# ProPrj__20260112_2026-01-12.net
KiCad netlist of a schematic drawn in EasyEDA Pro
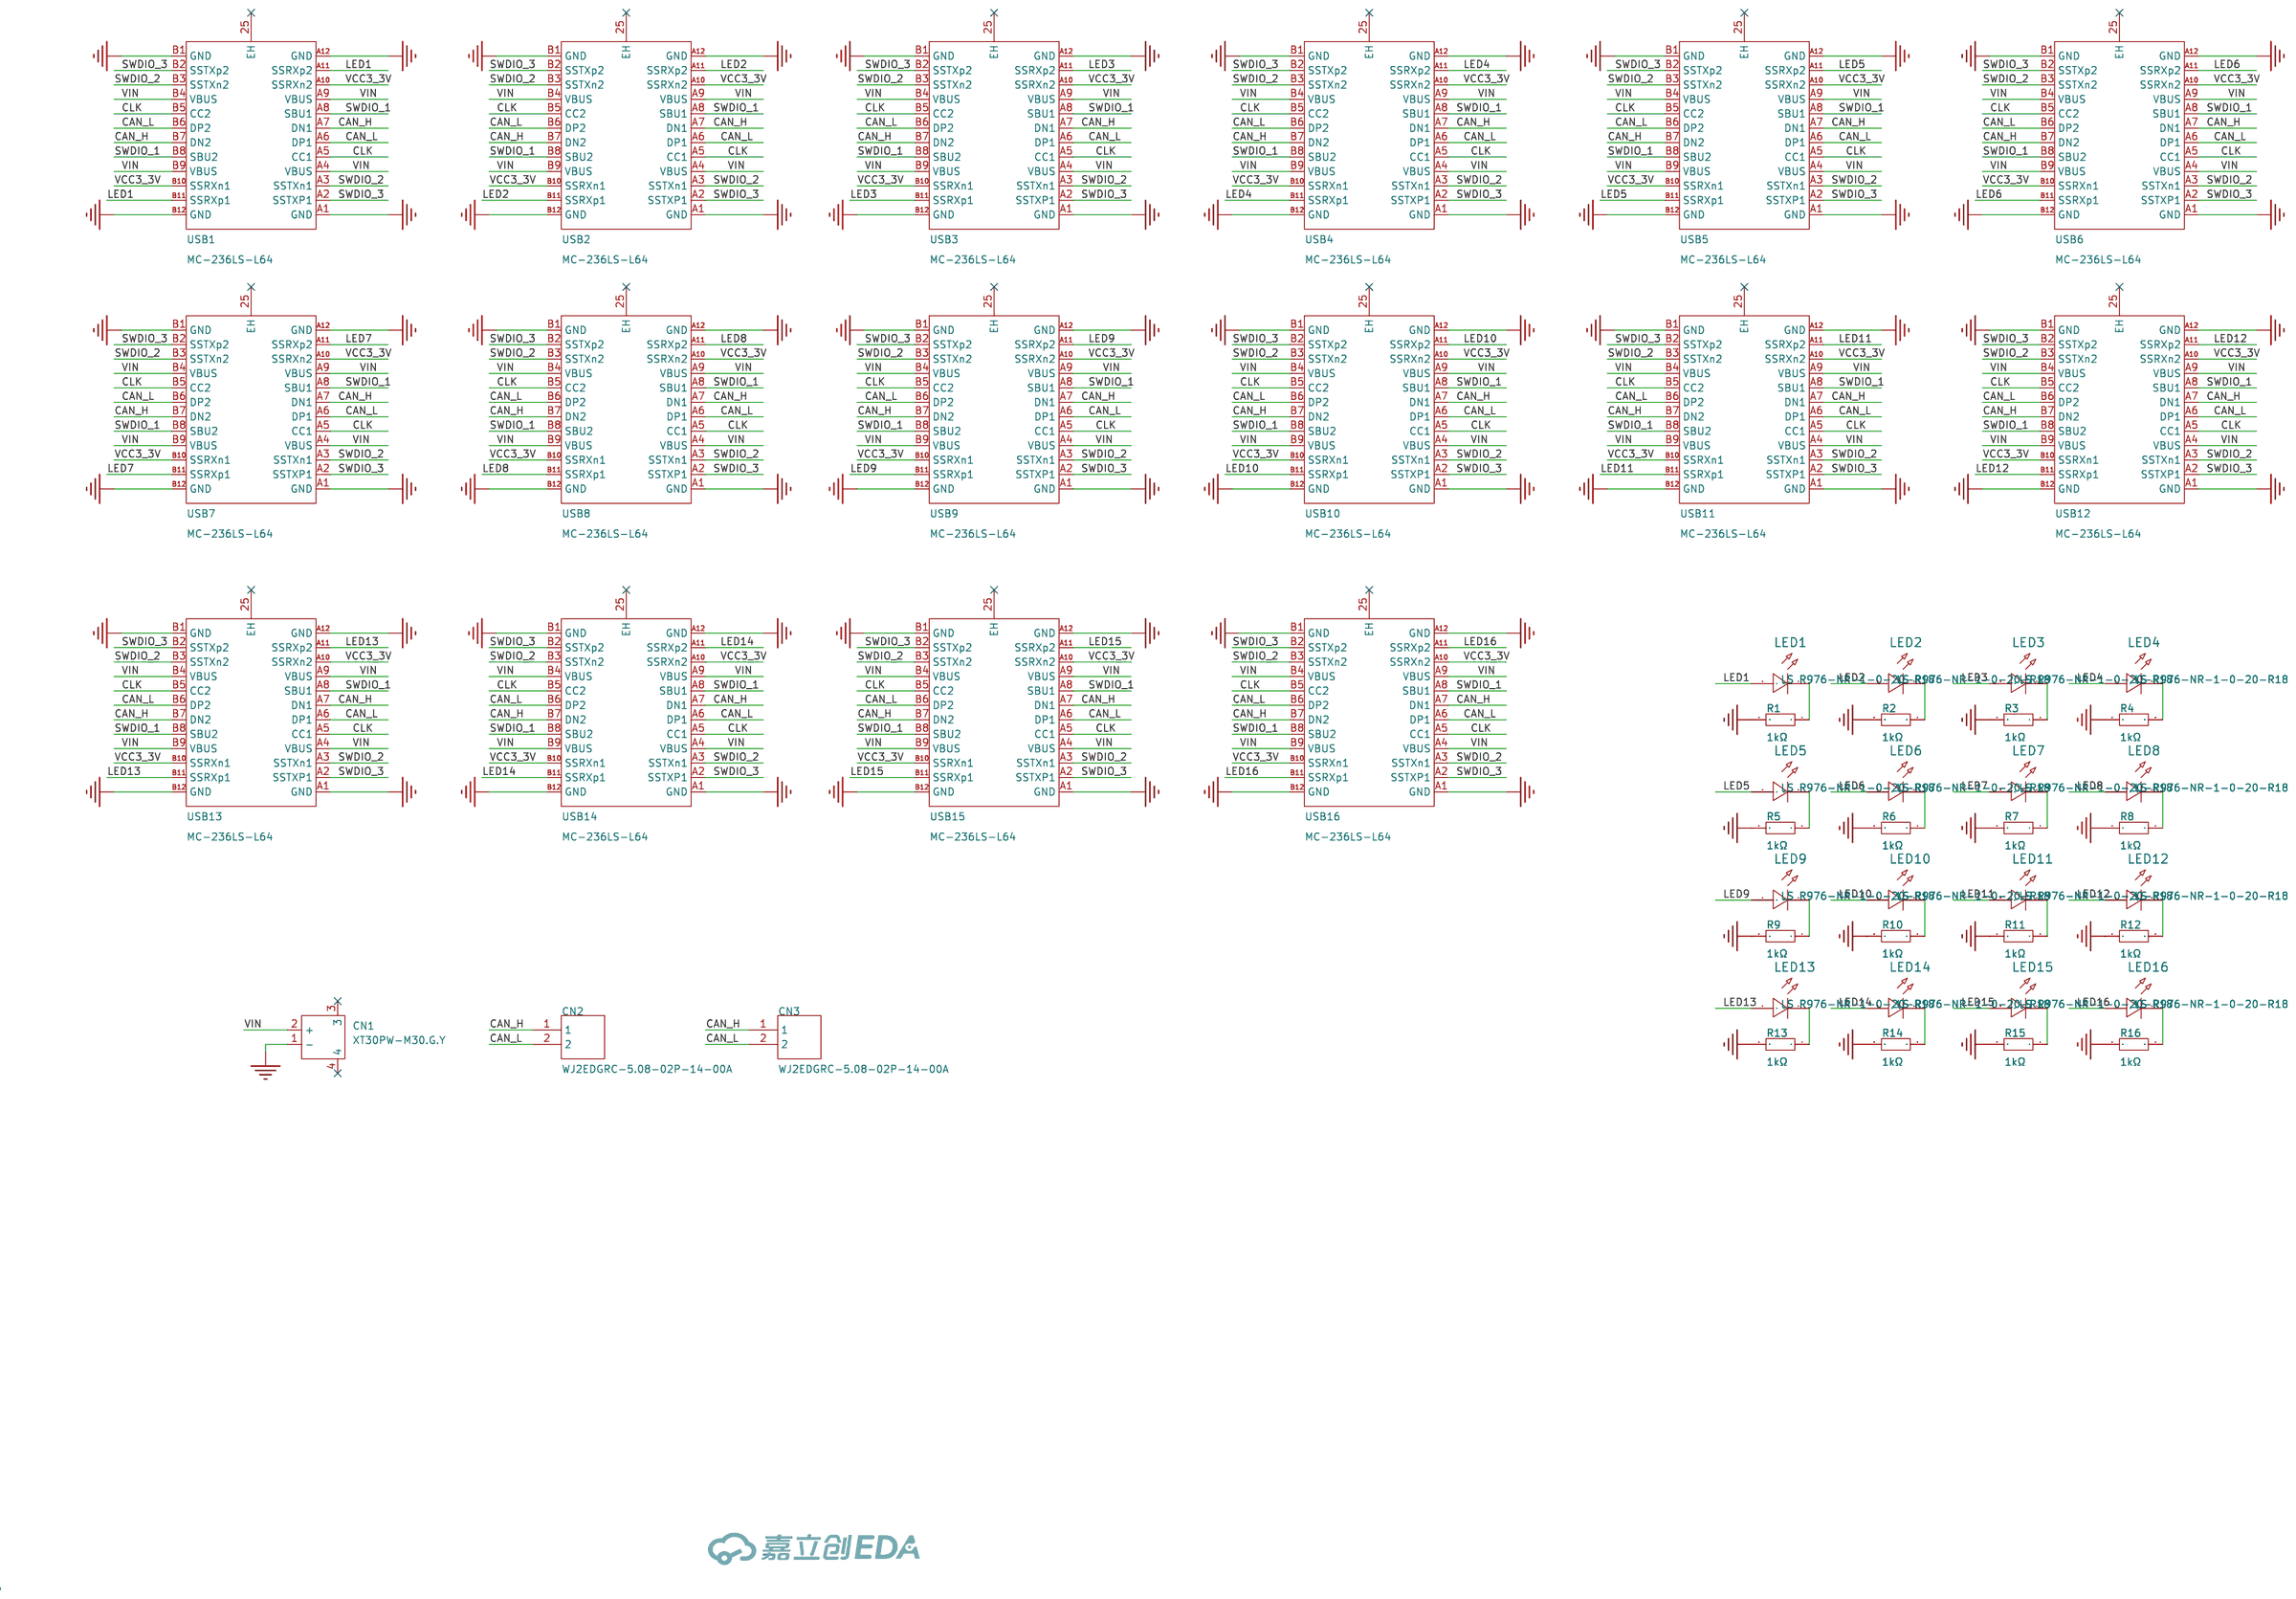
[diagram p0: schematic sheet]

(export (version "E")
  (design (tool "Eeschema 10.0.6"))
  (components
    (comp (ref "CN1")
      (value "XT30PW-M30.G.Y")
      (footprint "easyedapro:CONN-TH_XT30PW-M")
      (description "类别:-;类型1:-;")
      (fields (field (name "Manufacturer") "AMASS(艾迈斯)"))
      (libsource (lib "easyedapro") (part "XT30PW-M"))
    )
    (comp (ref "CN2")
      (value "WJ2EDGRC-5.08-02P-14-00A")
      (footprint "easyedapro:CONN-TH_2P-P5.08_WJ2EDGRC-5.08-2P")
      (fields (field (name "Manufacturer") "KANGNEX(康奈克斯电气)"))
      (libsource (lib "easyedapro") (part "WJ2EDGRC-5.08-2P"))
    )
    (comp (ref "CN3")
      (value "WJ2EDGRC-5.08-02P-14-00A")
      (footprint "easyedapro:CONN-TH_2P-P5.08_WJ2EDGRC-5.08-2P")
      (fields (field (name "Manufacturer") "KANGNEX(康奈克斯电气)"))
      (libsource (lib "easyedapro") (part "WJ2EDGRC-5.08-2P"))
    )
    (comp (ref "LED1")
      (value "LS R976-NR-1-0-20-R18")
      (footprint "easyedapro:LED_0805")
      (fields (field (name "Manufacturer") "OSRAM(欧司朗)"))
      (libsource (lib "easyedapro") (part "LED_R"))
    )
    (comp (ref "LED2")
      (value "LS R976-NR-1-0-20-R18")
      (footprint "easyedapro:LED_0805")
      (fields (field (name "Manufacturer") "OSRAM(欧司朗)"))
      (libsource (lib "easyedapro") (part "LED_R"))
    )
    (comp (ref "LED3")
      (value "LS R976-NR-1-0-20-R18")
      (footprint "easyedapro:LED_0805")
      (fields (field (name "Manufacturer") "OSRAM(欧司朗)"))
      (libsource (lib "easyedapro") (part "LED_R"))
    )
    (comp (ref "LED4")
      (value "LS R976-NR-1-0-20-R18")
      (footprint "easyedapro:LED_0805")
      (fields (field (name "Manufacturer") "OSRAM(欧司朗)"))
      (libsource (lib "easyedapro") (part "LED_R"))
    )
    (comp (ref "LED5")
      (value "LS R976-NR-1-0-20-R18")
      (footprint "easyedapro:LED_0805")
      (fields (field (name "Manufacturer") "OSRAM(欧司朗)"))
      (libsource (lib "easyedapro") (part "LED_R"))
    )
    (comp (ref "LED6")
      (value "LS R976-NR-1-0-20-R18")
      (footprint "easyedapro:LED_0805")
      (fields (field (name "Manufacturer") "OSRAM(欧司朗)"))
      (libsource (lib "easyedapro") (part "LED_R"))
    )
    (comp (ref "LED7")
      (value "LS R976-NR-1-0-20-R18")
      (footprint "easyedapro:LED_0805")
      (fields (field (name "Manufacturer") "OSRAM(欧司朗)"))
      (libsource (lib "easyedapro") (part "LED_R"))
    )
    (comp (ref "LED8")
      (value "LS R976-NR-1-0-20-R18")
      (footprint "easyedapro:LED_0805")
      (fields (field (name "Manufacturer") "OSRAM(欧司朗)"))
      (libsource (lib "easyedapro") (part "LED_R"))
    )
    (comp (ref "LED9")
      (value "LS R976-NR-1-0-20-R18")
      (footprint "easyedapro:LED_0805")
      (fields (field (name "Manufacturer") "OSRAM(欧司朗)"))
      (libsource (lib "easyedapro") (part "LED_R"))
    )
    (comp (ref "LED10")
      (value "LS R976-NR-1-0-20-R18")
      (footprint "easyedapro:LED_0805")
      (fields (field (name "Manufacturer") "OSRAM(欧司朗)"))
      (libsource (lib "easyedapro") (part "LED_R"))
    )
    (comp (ref "LED11")
      (value "LS R976-NR-1-0-20-R18")
      (footprint "easyedapro:LED_0805")
      (fields (field (name "Manufacturer") "OSRAM(欧司朗)"))
      (libsource (lib "easyedapro") (part "LED_R"))
    )
    (comp (ref "LED12")
      (value "LS R976-NR-1-0-20-R18")
      (footprint "easyedapro:LED_0805")
      (fields (field (name "Manufacturer") "OSRAM(欧司朗)"))
      (libsource (lib "easyedapro") (part "LED_R"))
    )
    (comp (ref "LED13")
      (value "LS R976-NR-1-0-20-R18")
      (footprint "easyedapro:LED_0805")
      (fields (field (name "Manufacturer") "OSRAM(欧司朗)"))
      (libsource (lib "easyedapro") (part "LED_R"))
    )
    (comp (ref "LED14")
      (value "LS R976-NR-1-0-20-R18")
      (footprint "easyedapro:LED_0805")
      (fields (field (name "Manufacturer") "OSRAM(欧司朗)"))
      (libsource (lib "easyedapro") (part "LED_R"))
    )
    (comp (ref "LED15")
      (value "LS R976-NR-1-0-20-R18")
      (footprint "easyedapro:LED_0805")
      (fields (field (name "Manufacturer") "OSRAM(欧司朗)"))
      (libsource (lib "easyedapro") (part "LED_R"))
    )
    (comp (ref "LED16")
      (value "LS R976-NR-1-0-20-R18")
      (footprint "easyedapro:LED_0805")
      (fields (field (name "Manufacturer") "OSRAM(欧司朗)"))
      (libsource (lib "easyedapro") (part "LED_R"))
    )
    (comp (ref "R1")
      (value "1kΩ")
      (footprint "easyedapro:R0805")
      (fields
        (field (name "Manufacturer Part") "0805W8F1001T5E")
        (field (name "Manufacturer") "UNI-ROYAL(厚声)")
      )
      (libsource (lib "easyedapro") (part "电阻"))
    )
    (comp (ref "R2")
      (value "1kΩ")
      (footprint "easyedapro:R0805")
      (fields
        (field (name "Manufacturer Part") "0805W8F1001T5E")
        (field (name "Manufacturer") "UNI-ROYAL(厚声)")
      )
      (libsource (lib "easyedapro") (part "电阻"))
    )
    (comp (ref "R3")
      (value "1kΩ")
      (footprint "easyedapro:R0805")
      (fields
        (field (name "Manufacturer Part") "0805W8F1001T5E")
        (field (name "Manufacturer") "UNI-ROYAL(厚声)")
      )
      (libsource (lib "easyedapro") (part "电阻"))
    )
    (comp (ref "R4")
      (value "1kΩ")
      (footprint "easyedapro:R0805")
      (fields
        (field (name "Manufacturer Part") "0805W8F1001T5E")
        (field (name "Manufacturer") "UNI-ROYAL(厚声)")
      )
      (libsource (lib "easyedapro") (part "电阻"))
    )
    (comp (ref "R5")
      (value "1kΩ")
      (footprint "easyedapro:R0805")
      (fields
        (field (name "Manufacturer Part") "0805W8F1001T5E")
        (field (name "Manufacturer") "UNI-ROYAL(厚声)")
      )
      (libsource (lib "easyedapro") (part "电阻"))
    )
    (comp (ref "R6")
      (value "1kΩ")
      (footprint "easyedapro:R0805")
      (fields
        (field (name "Manufacturer Part") "0805W8F1001T5E")
        (field (name "Manufacturer") "UNI-ROYAL(厚声)")
      )
      (libsource (lib "easyedapro") (part "电阻"))
    )
    (comp (ref "R7")
      (value "1kΩ")
      (footprint "easyedapro:R0805")
      (fields
        (field (name "Manufacturer Part") "0805W8F1001T5E")
        (field (name "Manufacturer") "UNI-ROYAL(厚声)")
      )
      (libsource (lib "easyedapro") (part "电阻"))
    )
    (comp (ref "R8")
      (value "1kΩ")
      (footprint "easyedapro:R0805")
      (fields
        (field (name "Manufacturer Part") "0805W8F1001T5E")
        (field (name "Manufacturer") "UNI-ROYAL(厚声)")
      )
      (libsource (lib "easyedapro") (part "电阻"))
    )
    (comp (ref "R9")
      (value "1kΩ")
      (footprint "easyedapro:R0805")
      (fields
        (field (name "Manufacturer Part") "0805W8F1001T5E")
        (field (name "Manufacturer") "UNI-ROYAL(厚声)")
      )
      (libsource (lib "easyedapro") (part "电阻"))
    )
    (comp (ref "R10")
      (value "1kΩ")
      (footprint "easyedapro:R0805")
      (fields
        (field (name "Manufacturer Part") "0805W8F1001T5E")
        (field (name "Manufacturer") "UNI-ROYAL(厚声)")
      )
      (libsource (lib "easyedapro") (part "电阻"))
    )
    (comp (ref "R11")
      (value "1kΩ")
      (footprint "easyedapro:R0805")
      (fields
        (field (name "Manufacturer Part") "0805W8F1001T5E")
        (field (name "Manufacturer") "UNI-ROYAL(厚声)")
      )
      (libsource (lib "easyedapro") (part "电阻"))
    )
    (comp (ref "R12")
      (value "1kΩ")
      (footprint "easyedapro:R0805")
      (fields
        (field (name "Manufacturer Part") "0805W8F1001T5E")
        (field (name "Manufacturer") "UNI-ROYAL(厚声)")
      )
      (libsource (lib "easyedapro") (part "电阻"))
    )
    (comp (ref "R13")
      (value "1kΩ")
      (footprint "easyedapro:R0805")
      (fields
        (field (name "Manufacturer Part") "0805W8F1001T5E")
        (field (name "Manufacturer") "UNI-ROYAL(厚声)")
      )
      (libsource (lib "easyedapro") (part "电阻"))
    )
    (comp (ref "R14")
      (value "1kΩ")
      (footprint "easyedapro:R0805")
      (fields
        (field (name "Manufacturer Part") "0805W8F1001T5E")
        (field (name "Manufacturer") "UNI-ROYAL(厚声)")
      )
      (libsource (lib "easyedapro") (part "电阻"))
    )
    (comp (ref "R15")
      (value "1kΩ")
      (footprint "easyedapro:R0805")
      (fields
        (field (name "Manufacturer Part") "0805W8F1001T5E")
        (field (name "Manufacturer") "UNI-ROYAL(厚声)")
      )
      (libsource (lib "easyedapro") (part "电阻"))
    )
    (comp (ref "R16")
      (value "1kΩ")
      (footprint "easyedapro:R0805")
      (fields
        (field (name "Manufacturer Part") "0805W8F1001T5E")
        (field (name "Manufacturer") "UNI-ROYAL(厚声)")
      )
      (libsource (lib "easyedapro") (part "电阻"))
    )
    (comp (ref "USB1")
      (value "MC-236LS-L64")
      (footprint "easyedapro:TYPE-C-USB-SMD_TYPE-C-31-M-06")
      (description "连接器类型:Type-C;协议标准:USB 3.1;公母:母;安装方式:立贴;触点数量:24P;端口数量:1;额定电流 - 电源:5A;工作温度:-25°C~+85°C;")
      (fields (field (name "Manufacturer") "HANBO(汉博)"))
      (libsource (lib "easyedapro") (part "MC-236LS-L64"))
    )
    (comp (ref "USB2")
      (value "MC-236LS-L64")
      (footprint "easyedapro:TYPE-C-USB-SMD_TYPE-C-31-M-06")
      (description "连接器类型:Type-C;协议标准:USB 3.1;公母:母;安装方式:立贴;触点数量:24P;端口数量:1;额定电流 - 电源:5A;工作温度:-25°C~+85°C;")
      (fields (field (name "Manufacturer") "HANBO(汉博)"))
      (libsource (lib "easyedapro") (part "MC-236LS-L64"))
    )
    (comp (ref "USB3")
      (value "MC-236LS-L64")
      (footprint "easyedapro:TYPE-C-USB-SMD_TYPE-C-31-M-06")
      (description "连接器类型:Type-C;协议标准:USB 3.1;公母:母;安装方式:立贴;触点数量:24P;端口数量:1;额定电流 - 电源:5A;工作温度:-25°C~+85°C;")
      (fields (field (name "Manufacturer") "HANBO(汉博)"))
      (libsource (lib "easyedapro") (part "MC-236LS-L64"))
    )
    (comp (ref "USB4")
      (value "MC-236LS-L64")
      (footprint "easyedapro:TYPE-C-USB-SMD_TYPE-C-31-M-06")
      (description "连接器类型:Type-C;协议标准:USB 3.1;公母:母;安装方式:立贴;触点数量:24P;端口数量:1;额定电流 - 电源:5A;工作温度:-25°C~+85°C;")
      (fields (field (name "Manufacturer") "HANBO(汉博)"))
      (libsource (lib "easyedapro") (part "MC-236LS-L64"))
    )
    (comp (ref "USB5")
      (value "MC-236LS-L64")
      (footprint "easyedapro:TYPE-C-USB-SMD_TYPE-C-31-M-06")
      (description "连接器类型:Type-C;协议标准:USB 3.1;公母:母;安装方式:立贴;触点数量:24P;端口数量:1;额定电流 - 电源:5A;工作温度:-25°C~+85°C;")
      (fields (field (name "Manufacturer") "HANBO(汉博)"))
      (libsource (lib "easyedapro") (part "MC-236LS-L64"))
    )
    (comp (ref "USB6")
      (value "MC-236LS-L64")
      (footprint "easyedapro:TYPE-C-USB-SMD_TYPE-C-31-M-06")
      (description "连接器类型:Type-C;协议标准:USB 3.1;公母:母;安装方式:立贴;触点数量:24P;端口数量:1;额定电流 - 电源:5A;工作温度:-25°C~+85°C;")
      (fields (field (name "Manufacturer") "HANBO(汉博)"))
      (libsource (lib "easyedapro") (part "MC-236LS-L64"))
    )
    (comp (ref "USB7")
      (value "MC-236LS-L64")
      (footprint "easyedapro:TYPE-C-USB-SMD_TYPE-C-31-M-06")
      (description "连接器类型:Type-C;协议标准:USB 3.1;公母:母;安装方式:立贴;触点数量:24P;端口数量:1;额定电流 - 电源:5A;工作温度:-25°C~+85°C;")
      (fields (field (name "Manufacturer") "HANBO(汉博)"))
      (libsource (lib "easyedapro") (part "MC-236LS-L64"))
    )
    (comp (ref "USB8")
      (value "MC-236LS-L64")
      (footprint "easyedapro:TYPE-C-USB-SMD_TYPE-C-31-M-06")
      (description "连接器类型:Type-C;协议标准:USB 3.1;公母:母;安装方式:立贴;触点数量:24P;端口数量:1;额定电流 - 电源:5A;工作温度:-25°C~+85°C;")
      (fields (field (name "Manufacturer") "HANBO(汉博)"))
      (libsource (lib "easyedapro") (part "MC-236LS-L64"))
    )
    (comp (ref "USB9")
      (value "MC-236LS-L64")
      (footprint "easyedapro:TYPE-C-USB-SMD_TYPE-C-31-M-06")
      (description "连接器类型:Type-C;协议标准:USB 3.1;公母:母;安装方式:立贴;触点数量:24P;端口数量:1;额定电流 - 电源:5A;工作温度:-25°C~+85°C;")
      (fields (field (name "Manufacturer") "HANBO(汉博)"))
      (libsource (lib "easyedapro") (part "MC-236LS-L64"))
    )
    (comp (ref "USB10")
      (value "MC-236LS-L64")
      (footprint "easyedapro:TYPE-C-USB-SMD_TYPE-C-31-M-06")
      (description "连接器类型:Type-C;协议标准:USB 3.1;公母:母;安装方式:立贴;触点数量:24P;端口数量:1;额定电流 - 电源:5A;工作温度:-25°C~+85°C;")
      (fields (field (name "Manufacturer") "HANBO(汉博)"))
      (libsource (lib "easyedapro") (part "MC-236LS-L64"))
    )
    (comp (ref "USB11")
      (value "MC-236LS-L64")
      (footprint "easyedapro:TYPE-C-USB-SMD_TYPE-C-31-M-06")
      (description "连接器类型:Type-C;协议标准:USB 3.1;公母:母;安装方式:立贴;触点数量:24P;端口数量:1;额定电流 - 电源:5A;工作温度:-25°C~+85°C;")
      (fields (field (name "Manufacturer") "HANBO(汉博)"))
      (libsource (lib "easyedapro") (part "MC-236LS-L64"))
    )
    (comp (ref "USB12")
      (value "MC-236LS-L64")
      (footprint "easyedapro:TYPE-C-USB-SMD_TYPE-C-31-M-06")
      (description "连接器类型:Type-C;协议标准:USB 3.1;公母:母;安装方式:立贴;触点数量:24P;端口数量:1;额定电流 - 电源:5A;工作温度:-25°C~+85°C;")
      (fields (field (name "Manufacturer") "HANBO(汉博)"))
      (libsource (lib "easyedapro") (part "MC-236LS-L64"))
    )
    (comp (ref "USB13")
      (value "MC-236LS-L64")
      (footprint "easyedapro:TYPE-C-USB-SMD_TYPE-C-31-M-06")
      (description "连接器类型:Type-C;协议标准:USB 3.1;公母:母;安装方式:立贴;触点数量:24P;端口数量:1;额定电流 - 电源:5A;工作温度:-25°C~+85°C;")
      (fields (field (name "Manufacturer") "HANBO(汉博)"))
      (libsource (lib "easyedapro") (part "MC-236LS-L64"))
    )
    (comp (ref "USB14")
      (value "MC-236LS-L64")
      (footprint "easyedapro:TYPE-C-USB-SMD_TYPE-C-31-M-06")
      (description "连接器类型:Type-C;协议标准:USB 3.1;公母:母;安装方式:立贴;触点数量:24P;端口数量:1;额定电流 - 电源:5A;工作温度:-25°C~+85°C;")
      (fields (field (name "Manufacturer") "HANBO(汉博)"))
      (libsource (lib "easyedapro") (part "MC-236LS-L64"))
    )
    (comp (ref "USB15")
      (value "MC-236LS-L64")
      (footprint "easyedapro:TYPE-C-USB-SMD_TYPE-C-31-M-06")
      (description "连接器类型:Type-C;协议标准:USB 3.1;公母:母;安装方式:立贴;触点数量:24P;端口数量:1;额定电流 - 电源:5A;工作温度:-25°C~+85°C;")
      (fields (field (name "Manufacturer") "HANBO(汉博)"))
      (libsource (lib "easyedapro") (part "MC-236LS-L64"))
    )
    (comp (ref "USB16")
      (value "MC-236LS-L64")
      (footprint "easyedapro:TYPE-C-USB-SMD_TYPE-C-31-M-06")
      (description "连接器类型:Type-C;协议标准:USB 3.1;公母:母;安装方式:立贴;触点数量:24P;端口数量:1;额定电流 - 电源:5A;工作温度:-25°C~+85°C;")
      (fields (field (name "Manufacturer") "HANBO(汉博)"))
      (libsource (lib "easyedapro") (part "MC-236LS-L64"))
    )
  )
  (nets
    (net (code "1") (name "/CAN_H") (class "Default")
      (node (ref "CN2") (pin "1") (pinfunction "1_1") (pintype "unspecified"))
      (node (ref "CN3") (pin "1") (pinfunction "1_1") (pintype "unspecified"))
      (node (ref "USB1") (pin "A7") (pinfunction "DN1_A7") (pintype "unspecified"))
      (node (ref "USB1") (pin "B7") (pinfunction "DN2_B7") (pintype "unspecified"))
      (node (ref "USB10") (pin "A7") (pinfunction "DN1_A7") (pintype "unspecified"))
      (node (ref "USB10") (pin "B7") (pinfunction "DN2_B7") (pintype "unspecified"))
      (node (ref "USB11") (pin "A7") (pinfunction "DN1_A7") (pintype "unspecified"))
      (node (ref "USB11") (pin "B7") (pinfunction "DN2_B7") (pintype "unspecified"))
      (node (ref "USB12") (pin "A7") (pinfunction "DN1_A7") (pintype "unspecified"))
      (node (ref "USB12") (pin "B7") (pinfunction "DN2_B7") (pintype "unspecified"))
      (node (ref "USB13") (pin "A7") (pinfunction "DN1_A7") (pintype "unspecified"))
      (node (ref "USB13") (pin "B7") (pinfunction "DN2_B7") (pintype "unspecified"))
      (node (ref "USB14") (pin "A7") (pinfunction "DN1_A7") (pintype "unspecified"))
      (node (ref "USB14") (pin "B7") (pinfunction "DN2_B7") (pintype "unspecified"))
      (node (ref "USB15") (pin "A7") (pinfunction "DN1_A7") (pintype "unspecified"))
      (node (ref "USB15") (pin "B7") (pinfunction "DN2_B7") (pintype "unspecified"))
      (node (ref "USB16") (pin "A7") (pinfunction "DN1_A7") (pintype "unspecified"))
      (node (ref "USB16") (pin "B7") (pinfunction "DN2_B7") (pintype "unspecified"))
      (node (ref "USB2") (pin "A7") (pinfunction "DN1_A7") (pintype "unspecified"))
      (node (ref "USB2") (pin "B7") (pinfunction "DN2_B7") (pintype "unspecified"))
      (node (ref "USB3") (pin "A7") (pinfunction "DN1_A7") (pintype "unspecified"))
      (node (ref "USB3") (pin "B7") (pinfunction "DN2_B7") (pintype "unspecified"))
      (node (ref "USB4") (pin "A7") (pinfunction "DN1_A7") (pintype "unspecified"))
      (node (ref "USB4") (pin "B7") (pinfunction "DN2_B7") (pintype "unspecified"))
      (node (ref "USB5") (pin "A7") (pinfunction "DN1_A7") (pintype "unspecified"))
      (node (ref "USB5") (pin "B7") (pinfunction "DN2_B7") (pintype "unspecified"))
      (node (ref "USB6") (pin "A7") (pinfunction "DN1_A7") (pintype "unspecified"))
      (node (ref "USB6") (pin "B7") (pinfunction "DN2_B7") (pintype "unspecified"))
      (node (ref "USB7") (pin "A7") (pinfunction "DN1_A7") (pintype "unspecified"))
      (node (ref "USB7") (pin "B7") (pinfunction "DN2_B7") (pintype "unspecified"))
      (node (ref "USB8") (pin "A7") (pinfunction "DN1_A7") (pintype "unspecified"))
      (node (ref "USB8") (pin "B7") (pinfunction "DN2_B7") (pintype "unspecified"))
      (node (ref "USB9") (pin "A7") (pinfunction "DN1_A7") (pintype "unspecified"))
      (node (ref "USB9") (pin "B7") (pinfunction "DN2_B7") (pintype "unspecified"))
    )
    (net (code "2") (name "/CAN_L") (class "Default")
      (node (ref "CN2") (pin "2") (pinfunction "2_2") (pintype "unspecified"))
      (node (ref "CN3") (pin "2") (pinfunction "2_2") (pintype "unspecified"))
      (node (ref "USB1") (pin "A6") (pinfunction "DP1_A6") (pintype "unspecified"))
      (node (ref "USB1") (pin "B6") (pinfunction "DP2_B6") (pintype "unspecified"))
      (node (ref "USB10") (pin "A6") (pinfunction "DP1_A6") (pintype "unspecified"))
      (node (ref "USB10") (pin "B6") (pinfunction "DP2_B6") (pintype "unspecified"))
      (node (ref "USB11") (pin "A6") (pinfunction "DP1_A6") (pintype "unspecified"))
      (node (ref "USB11") (pin "B6") (pinfunction "DP2_B6") (pintype "unspecified"))
      (node (ref "USB12") (pin "A6") (pinfunction "DP1_A6") (pintype "unspecified"))
      (node (ref "USB12") (pin "B6") (pinfunction "DP2_B6") (pintype "unspecified"))
      (node (ref "USB13") (pin "A6") (pinfunction "DP1_A6") (pintype "unspecified"))
      (node (ref "USB13") (pin "B6") (pinfunction "DP2_B6") (pintype "unspecified"))
      (node (ref "USB14") (pin "A6") (pinfunction "DP1_A6") (pintype "unspecified"))
      (node (ref "USB14") (pin "B6") (pinfunction "DP2_B6") (pintype "unspecified"))
      (node (ref "USB15") (pin "A6") (pinfunction "DP1_A6") (pintype "unspecified"))
      (node (ref "USB15") (pin "B6") (pinfunction "DP2_B6") (pintype "unspecified"))
      (node (ref "USB16") (pin "A6") (pinfunction "DP1_A6") (pintype "unspecified"))
      (node (ref "USB16") (pin "B6") (pinfunction "DP2_B6") (pintype "unspecified"))
      (node (ref "USB2") (pin "A6") (pinfunction "DP1_A6") (pintype "unspecified"))
      (node (ref "USB2") (pin "B6") (pinfunction "DP2_B6") (pintype "unspecified"))
      (node (ref "USB3") (pin "A6") (pinfunction "DP1_A6") (pintype "unspecified"))
      (node (ref "USB3") (pin "B6") (pinfunction "DP2_B6") (pintype "unspecified"))
      (node (ref "USB4") (pin "A6") (pinfunction "DP1_A6") (pintype "unspecified"))
      (node (ref "USB4") (pin "B6") (pinfunction "DP2_B6") (pintype "unspecified"))
      (node (ref "USB5") (pin "A6") (pinfunction "DP1_A6") (pintype "unspecified"))
      (node (ref "USB5") (pin "B6") (pinfunction "DP2_B6") (pintype "unspecified"))
      (node (ref "USB6") (pin "A6") (pinfunction "DP1_A6") (pintype "unspecified"))
      (node (ref "USB6") (pin "B6") (pinfunction "DP2_B6") (pintype "unspecified"))
      (node (ref "USB7") (pin "A6") (pinfunction "DP1_A6") (pintype "unspecified"))
      (node (ref "USB7") (pin "B6") (pinfunction "DP2_B6") (pintype "unspecified"))
      (node (ref "USB8") (pin "A6") (pinfunction "DP1_A6") (pintype "unspecified"))
      (node (ref "USB8") (pin "B6") (pinfunction "DP2_B6") (pintype "unspecified"))
      (node (ref "USB9") (pin "A6") (pinfunction "DP1_A6") (pintype "unspecified"))
      (node (ref "USB9") (pin "B6") (pinfunction "DP2_B6") (pintype "unspecified"))
    )
    (net (code "3") (name "/CLK") (class "Default")
      (node (ref "USB1") (pin "A5") (pinfunction "CC1_A5") (pintype "unspecified"))
      (node (ref "USB1") (pin "B5") (pinfunction "CC2_B5") (pintype "unspecified"))
      (node (ref "USB10") (pin "A5") (pinfunction "CC1_A5") (pintype "unspecified"))
      (node (ref "USB10") (pin "B5") (pinfunction "CC2_B5") (pintype "unspecified"))
      (node (ref "USB11") (pin "A5") (pinfunction "CC1_A5") (pintype "unspecified"))
      (node (ref "USB11") (pin "B5") (pinfunction "CC2_B5") (pintype "unspecified"))
      (node (ref "USB12") (pin "A5") (pinfunction "CC1_A5") (pintype "unspecified"))
      (node (ref "USB12") (pin "B5") (pinfunction "CC2_B5") (pintype "unspecified"))
      (node (ref "USB13") (pin "A5") (pinfunction "CC1_A5") (pintype "unspecified"))
      (node (ref "USB13") (pin "B5") (pinfunction "CC2_B5") (pintype "unspecified"))
      (node (ref "USB14") (pin "A5") (pinfunction "CC1_A5") (pintype "unspecified"))
      (node (ref "USB14") (pin "B5") (pinfunction "CC2_B5") (pintype "unspecified"))
      (node (ref "USB15") (pin "A5") (pinfunction "CC1_A5") (pintype "unspecified"))
      (node (ref "USB15") (pin "B5") (pinfunction "CC2_B5") (pintype "unspecified"))
      (node (ref "USB16") (pin "A5") (pinfunction "CC1_A5") (pintype "unspecified"))
      (node (ref "USB16") (pin "B5") (pinfunction "CC2_B5") (pintype "unspecified"))
      (node (ref "USB2") (pin "A5") (pinfunction "CC1_A5") (pintype "unspecified"))
      (node (ref "USB2") (pin "B5") (pinfunction "CC2_B5") (pintype "unspecified"))
      (node (ref "USB3") (pin "A5") (pinfunction "CC1_A5") (pintype "unspecified"))
      (node (ref "USB3") (pin "B5") (pinfunction "CC2_B5") (pintype "unspecified"))
      (node (ref "USB4") (pin "A5") (pinfunction "CC1_A5") (pintype "unspecified"))
      (node (ref "USB4") (pin "B5") (pinfunction "CC2_B5") (pintype "unspecified"))
      (node (ref "USB5") (pin "A5") (pinfunction "CC1_A5") (pintype "unspecified"))
      (node (ref "USB5") (pin "B5") (pinfunction "CC2_B5") (pintype "unspecified"))
      (node (ref "USB6") (pin "A5") (pinfunction "CC1_A5") (pintype "unspecified"))
      (node (ref "USB6") (pin "B5") (pinfunction "CC2_B5") (pintype "unspecified"))
      (node (ref "USB7") (pin "A5") (pinfunction "CC1_A5") (pintype "unspecified"))
      (node (ref "USB7") (pin "B5") (pinfunction "CC2_B5") (pintype "unspecified"))
      (node (ref "USB8") (pin "A5") (pinfunction "CC1_A5") (pintype "unspecified"))
      (node (ref "USB8") (pin "B5") (pinfunction "CC2_B5") (pintype "unspecified"))
      (node (ref "USB9") (pin "A5") (pinfunction "CC1_A5") (pintype "unspecified"))
      (node (ref "USB9") (pin "B5") (pinfunction "CC2_B5") (pintype "unspecified"))
    )
    (net (code "4") (name "/LED1") (class "Default")
      (node (ref "LED1") (pin "2") (pinfunction "A_2") (pintype "input"))
      (node (ref "USB1") (pin "A11") (pinfunction "SSRXp2_A11") (pintype "unspecified"))
      (node (ref "USB1") (pin "B11") (pinfunction "SSRXp1_B11") (pintype "unspecified"))
    )
    (net (code "5") (name "/LED2") (class "Default")
      (node (ref "LED2") (pin "2") (pinfunction "A_2") (pintype "input"))
      (node (ref "USB2") (pin "A11") (pinfunction "SSRXp2_A11") (pintype "unspecified"))
      (node (ref "USB2") (pin "B11") (pinfunction "SSRXp1_B11") (pintype "unspecified"))
    )
    (net (code "6") (name "/LED3") (class "Default")
      (node (ref "LED3") (pin "2") (pinfunction "A_2") (pintype "input"))
      (node (ref "USB3") (pin "A11") (pinfunction "SSRXp2_A11") (pintype "unspecified"))
      (node (ref "USB3") (pin "B11") (pinfunction "SSRXp1_B11") (pintype "unspecified"))
    )
    (net (code "7") (name "/LED4") (class "Default")
      (node (ref "LED4") (pin "2") (pinfunction "A_2") (pintype "input"))
      (node (ref "USB4") (pin "A11") (pinfunction "SSRXp2_A11") (pintype "unspecified"))
      (node (ref "USB4") (pin "B11") (pinfunction "SSRXp1_B11") (pintype "unspecified"))
    )
    (net (code "8") (name "/LED5") (class "Default")
      (node (ref "LED5") (pin "2") (pinfunction "A_2") (pintype "input"))
      (node (ref "USB5") (pin "A11") (pinfunction "SSRXp2_A11") (pintype "unspecified"))
      (node (ref "USB5") (pin "B11") (pinfunction "SSRXp1_B11") (pintype "unspecified"))
    )
    (net (code "9") (name "/LED6") (class "Default")
      (node (ref "LED6") (pin "2") (pinfunction "A_2") (pintype "input"))
      (node (ref "USB6") (pin "A11") (pinfunction "SSRXp2_A11") (pintype "unspecified"))
      (node (ref "USB6") (pin "B11") (pinfunction "SSRXp1_B11") (pintype "unspecified"))
    )
    (net (code "10") (name "/LED7") (class "Default")
      (node (ref "LED7") (pin "2") (pinfunction "A_2") (pintype "input"))
      (node (ref "USB7") (pin "A11") (pinfunction "SSRXp2_A11") (pintype "unspecified"))
      (node (ref "USB7") (pin "B11") (pinfunction "SSRXp1_B11") (pintype "unspecified"))
    )
    (net (code "11") (name "/LED8") (class "Default")
      (node (ref "LED8") (pin "2") (pinfunction "A_2") (pintype "input"))
      (node (ref "USB8") (pin "A11") (pinfunction "SSRXp2_A11") (pintype "unspecified"))
      (node (ref "USB8") (pin "B11") (pinfunction "SSRXp1_B11") (pintype "unspecified"))
    )
    (net (code "12") (name "/LED9") (class "Default")
      (node (ref "LED9") (pin "2") (pinfunction "A_2") (pintype "input"))
      (node (ref "USB9") (pin "A11") (pinfunction "SSRXp2_A11") (pintype "unspecified"))
      (node (ref "USB9") (pin "B11") (pinfunction "SSRXp1_B11") (pintype "unspecified"))
    )
    (net (code "13") (name "/LED10") (class "Default")
      (node (ref "LED10") (pin "2") (pinfunction "A_2") (pintype "input"))
      (node (ref "USB10") (pin "A11") (pinfunction "SSRXp2_A11") (pintype "unspecified"))
      (node (ref "USB10") (pin "B11") (pinfunction "SSRXp1_B11") (pintype "unspecified"))
    )
    (net (code "14") (name "/LED11") (class "Default")
      (node (ref "LED11") (pin "2") (pinfunction "A_2") (pintype "input"))
      (node (ref "USB11") (pin "A11") (pinfunction "SSRXp2_A11") (pintype "unspecified"))
      (node (ref "USB11") (pin "B11") (pinfunction "SSRXp1_B11") (pintype "unspecified"))
    )
    (net (code "15") (name "/LED12") (class "Default")
      (node (ref "LED12") (pin "2") (pinfunction "A_2") (pintype "input"))
      (node (ref "USB12") (pin "A11") (pinfunction "SSRXp2_A11") (pintype "unspecified"))
      (node (ref "USB12") (pin "B11") (pinfunction "SSRXp1_B11") (pintype "unspecified"))
    )
    (net (code "16") (name "/LED13") (class "Default")
      (node (ref "LED13") (pin "2") (pinfunction "A_2") (pintype "input"))
      (node (ref "USB13") (pin "A11") (pinfunction "SSRXp2_A11") (pintype "unspecified"))
      (node (ref "USB13") (pin "B11") (pinfunction "SSRXp1_B11") (pintype "unspecified"))
    )
    (net (code "17") (name "/LED14") (class "Default")
      (node (ref "LED14") (pin "2") (pinfunction "A_2") (pintype "input"))
      (node (ref "USB14") (pin "A11") (pinfunction "SSRXp2_A11") (pintype "unspecified"))
      (node (ref "USB14") (pin "B11") (pinfunction "SSRXp1_B11") (pintype "unspecified"))
    )
    (net (code "18") (name "/LED15") (class "Default")
      (node (ref "LED15") (pin "2") (pinfunction "A_2") (pintype "input"))
      (node (ref "USB15") (pin "A11") (pinfunction "SSRXp2_A11") (pintype "unspecified"))
      (node (ref "USB15") (pin "B11") (pinfunction "SSRXp1_B11") (pintype "unspecified"))
    )
    (net (code "19") (name "/LED16") (class "Default")
      (node (ref "LED16") (pin "2") (pinfunction "A_2") (pintype "input"))
      (node (ref "USB16") (pin "A11") (pinfunction "SSRXp2_A11") (pintype "unspecified"))
      (node (ref "USB16") (pin "B11") (pinfunction "SSRXp1_B11") (pintype "unspecified"))
    )
    (net (code "20") (name "/SWDIO_1") (class "Default")
      (node (ref "USB1") (pin "A8") (pinfunction "SBU1_A8") (pintype "unspecified"))
      (node (ref "USB1") (pin "B8") (pinfunction "SBU2_B8") (pintype "unspecified"))
      (node (ref "USB10") (pin "A8") (pinfunction "SBU1_A8") (pintype "unspecified"))
      (node (ref "USB10") (pin "B8") (pinfunction "SBU2_B8") (pintype "unspecified"))
      (node (ref "USB11") (pin "A8") (pinfunction "SBU1_A8") (pintype "unspecified"))
      (node (ref "USB11") (pin "B8") (pinfunction "SBU2_B8") (pintype "unspecified"))
      (node (ref "USB12") (pin "A8") (pinfunction "SBU1_A8") (pintype "unspecified"))
      (node (ref "USB12") (pin "B8") (pinfunction "SBU2_B8") (pintype "unspecified"))
      (node (ref "USB13") (pin "A8") (pinfunction "SBU1_A8") (pintype "unspecified"))
      (node (ref "USB13") (pin "B8") (pinfunction "SBU2_B8") (pintype "unspecified"))
      (node (ref "USB14") (pin "A8") (pinfunction "SBU1_A8") (pintype "unspecified"))
      (node (ref "USB14") (pin "B8") (pinfunction "SBU2_B8") (pintype "unspecified"))
      (node (ref "USB15") (pin "A8") (pinfunction "SBU1_A8") (pintype "unspecified"))
      (node (ref "USB15") (pin "B8") (pinfunction "SBU2_B8") (pintype "unspecified"))
      (node (ref "USB16") (pin "A8") (pinfunction "SBU1_A8") (pintype "unspecified"))
      (node (ref "USB16") (pin "B8") (pinfunction "SBU2_B8") (pintype "unspecified"))
      (node (ref "USB2") (pin "A8") (pinfunction "SBU1_A8") (pintype "unspecified"))
      (node (ref "USB2") (pin "B8") (pinfunction "SBU2_B8") (pintype "unspecified"))
      (node (ref "USB3") (pin "A8") (pinfunction "SBU1_A8") (pintype "unspecified"))
      (node (ref "USB3") (pin "B8") (pinfunction "SBU2_B8") (pintype "unspecified"))
      (node (ref "USB4") (pin "A8") (pinfunction "SBU1_A8") (pintype "unspecified"))
      (node (ref "USB4") (pin "B8") (pinfunction "SBU2_B8") (pintype "unspecified"))
      (node (ref "USB5") (pin "A8") (pinfunction "SBU1_A8") (pintype "unspecified"))
      (node (ref "USB5") (pin "B8") (pinfunction "SBU2_B8") (pintype "unspecified"))
      (node (ref "USB6") (pin "A8") (pinfunction "SBU1_A8") (pintype "unspecified"))
      (node (ref "USB6") (pin "B8") (pinfunction "SBU2_B8") (pintype "unspecified"))
      (node (ref "USB7") (pin "A8") (pinfunction "SBU1_A8") (pintype "unspecified"))
      (node (ref "USB7") (pin "B8") (pinfunction "SBU2_B8") (pintype "unspecified"))
      (node (ref "USB8") (pin "A8") (pinfunction "SBU1_A8") (pintype "unspecified"))
      (node (ref "USB8") (pin "B8") (pinfunction "SBU2_B8") (pintype "unspecified"))
      (node (ref "USB9") (pin "A8") (pinfunction "SBU1_A8") (pintype "unspecified"))
      (node (ref "USB9") (pin "B8") (pinfunction "SBU2_B8") (pintype "unspecified"))
    )
    (net (code "21") (name "/SWDIO_2") (class "Default")
      (node (ref "USB1") (pin "A3") (pinfunction "SSTXn1_A3") (pintype "unspecified"))
      (node (ref "USB1") (pin "B3") (pinfunction "SSTXn2_B3") (pintype "unspecified"))
      (node (ref "USB10") (pin "A3") (pinfunction "SSTXn1_A3") (pintype "unspecified"))
      (node (ref "USB10") (pin "B3") (pinfunction "SSTXn2_B3") (pintype "unspecified"))
      (node (ref "USB11") (pin "A3") (pinfunction "SSTXn1_A3") (pintype "unspecified"))
      (node (ref "USB11") (pin "B3") (pinfunction "SSTXn2_B3") (pintype "unspecified"))
      (node (ref "USB12") (pin "A3") (pinfunction "SSTXn1_A3") (pintype "unspecified"))
      (node (ref "USB12") (pin "B3") (pinfunction "SSTXn2_B3") (pintype "unspecified"))
      (node (ref "USB13") (pin "A3") (pinfunction "SSTXn1_A3") (pintype "unspecified"))
      (node (ref "USB13") (pin "B3") (pinfunction "SSTXn2_B3") (pintype "unspecified"))
      (node (ref "USB14") (pin "A3") (pinfunction "SSTXn1_A3") (pintype "unspecified"))
      (node (ref "USB14") (pin "B3") (pinfunction "SSTXn2_B3") (pintype "unspecified"))
      (node (ref "USB15") (pin "A3") (pinfunction "SSTXn1_A3") (pintype "unspecified"))
      (node (ref "USB15") (pin "B3") (pinfunction "SSTXn2_B3") (pintype "unspecified"))
      (node (ref "USB16") (pin "A3") (pinfunction "SSTXn1_A3") (pintype "unspecified"))
      (node (ref "USB16") (pin "B3") (pinfunction "SSTXn2_B3") (pintype "unspecified"))
      (node (ref "USB2") (pin "A3") (pinfunction "SSTXn1_A3") (pintype "unspecified"))
      (node (ref "USB2") (pin "B3") (pinfunction "SSTXn2_B3") (pintype "unspecified"))
      (node (ref "USB3") (pin "A3") (pinfunction "SSTXn1_A3") (pintype "unspecified"))
      (node (ref "USB3") (pin "B3") (pinfunction "SSTXn2_B3") (pintype "unspecified"))
      (node (ref "USB4") (pin "A3") (pinfunction "SSTXn1_A3") (pintype "unspecified"))
      (node (ref "USB4") (pin "B3") (pinfunction "SSTXn2_B3") (pintype "unspecified"))
      (node (ref "USB5") (pin "A3") (pinfunction "SSTXn1_A3") (pintype "unspecified"))
      (node (ref "USB5") (pin "B3") (pinfunction "SSTXn2_B3") (pintype "unspecified"))
      (node (ref "USB6") (pin "A3") (pinfunction "SSTXn1_A3") (pintype "unspecified"))
      (node (ref "USB6") (pin "B3") (pinfunction "SSTXn2_B3") (pintype "unspecified"))
      (node (ref "USB7") (pin "A3") (pinfunction "SSTXn1_A3") (pintype "unspecified"))
      (node (ref "USB7") (pin "B3") (pinfunction "SSTXn2_B3") (pintype "unspecified"))
      (node (ref "USB8") (pin "A3") (pinfunction "SSTXn1_A3") (pintype "unspecified"))
      (node (ref "USB8") (pin "B3") (pinfunction "SSTXn2_B3") (pintype "unspecified"))
      (node (ref "USB9") (pin "A3") (pinfunction "SSTXn1_A3") (pintype "unspecified"))
      (node (ref "USB9") (pin "B3") (pinfunction "SSTXn2_B3") (pintype "unspecified"))
    )
    (net (code "22") (name "/SWDIO_3") (class "Default")
      (node (ref "USB1") (pin "A2") (pinfunction "SSTXP1_A2") (pintype "unspecified"))
      (node (ref "USB1") (pin "B2") (pinfunction "SSTXp2_B2") (pintype "unspecified"))
      (node (ref "USB10") (pin "A2") (pinfunction "SSTXP1_A2") (pintype "unspecified"))
      (node (ref "USB10") (pin "B2") (pinfunction "SSTXp2_B2") (pintype "unspecified"))
      (node (ref "USB11") (pin "A2") (pinfunction "SSTXP1_A2") (pintype "unspecified"))
      (node (ref "USB11") (pin "B2") (pinfunction "SSTXp2_B2") (pintype "unspecified"))
      (node (ref "USB12") (pin "A2") (pinfunction "SSTXP1_A2") (pintype "unspecified"))
      (node (ref "USB12") (pin "B2") (pinfunction "SSTXp2_B2") (pintype "unspecified"))
      (node (ref "USB13") (pin "A2") (pinfunction "SSTXP1_A2") (pintype "unspecified"))
      (node (ref "USB13") (pin "B2") (pinfunction "SSTXp2_B2") (pintype "unspecified"))
      (node (ref "USB14") (pin "A2") (pinfunction "SSTXP1_A2") (pintype "unspecified"))
      (node (ref "USB14") (pin "B2") (pinfunction "SSTXp2_B2") (pintype "unspecified"))
      (node (ref "USB15") (pin "A2") (pinfunction "SSTXP1_A2") (pintype "unspecified"))
      (node (ref "USB15") (pin "B2") (pinfunction "SSTXp2_B2") (pintype "unspecified"))
      (node (ref "USB16") (pin "A2") (pinfunction "SSTXP1_A2") (pintype "unspecified"))
      (node (ref "USB16") (pin "B2") (pinfunction "SSTXp2_B2") (pintype "unspecified"))
      (node (ref "USB2") (pin "A2") (pinfunction "SSTXP1_A2") (pintype "unspecified"))
      (node (ref "USB2") (pin "B2") (pinfunction "SSTXp2_B2") (pintype "unspecified"))
      (node (ref "USB3") (pin "A2") (pinfunction "SSTXP1_A2") (pintype "unspecified"))
      (node (ref "USB3") (pin "B2") (pinfunction "SSTXp2_B2") (pintype "unspecified"))
      (node (ref "USB4") (pin "A2") (pinfunction "SSTXP1_A2") (pintype "unspecified"))
      (node (ref "USB4") (pin "B2") (pinfunction "SSTXp2_B2") (pintype "unspecified"))
      (node (ref "USB5") (pin "A2") (pinfunction "SSTXP1_A2") (pintype "unspecified"))
      (node (ref "USB5") (pin "B2") (pinfunction "SSTXp2_B2") (pintype "unspecified"))
      (node (ref "USB6") (pin "A2") (pinfunction "SSTXP1_A2") (pintype "unspecified"))
      (node (ref "USB6") (pin "B2") (pinfunction "SSTXp2_B2") (pintype "unspecified"))
      (node (ref "USB7") (pin "A2") (pinfunction "SSTXP1_A2") (pintype "unspecified"))
      (node (ref "USB7") (pin "B2") (pinfunction "SSTXp2_B2") (pintype "unspecified"))
      (node (ref "USB8") (pin "A2") (pinfunction "SSTXP1_A2") (pintype "unspecified"))
      (node (ref "USB8") (pin "B2") (pinfunction "SSTXp2_B2") (pintype "unspecified"))
      (node (ref "USB9") (pin "A2") (pinfunction "SSTXP1_A2") (pintype "unspecified"))
      (node (ref "USB9") (pin "B2") (pinfunction "SSTXp2_B2") (pintype "unspecified"))
    )
    (net (code "23") (name "/VCC3_3V") (class "Default")
      (node (ref "USB1") (pin "A10") (pinfunction "SSRXn2_A10") (pintype "unspecified"))
      (node (ref "USB1") (pin "B10") (pinfunction "SSRXn1_B10") (pintype "unspecified"))
      (node (ref "USB10") (pin "A10") (pinfunction "SSRXn2_A10") (pintype "unspecified"))
      (node (ref "USB10") (pin "B10") (pinfunction "SSRXn1_B10") (pintype "unspecified"))
      (node (ref "USB11") (pin "A10") (pinfunction "SSRXn2_A10") (pintype "unspecified"))
      (node (ref "USB11") (pin "B10") (pinfunction "SSRXn1_B10") (pintype "unspecified"))
      (node (ref "USB12") (pin "A10") (pinfunction "SSRXn2_A10") (pintype "unspecified"))
      (node (ref "USB12") (pin "B10") (pinfunction "SSRXn1_B10") (pintype "unspecified"))
      (node (ref "USB13") (pin "A10") (pinfunction "SSRXn2_A10") (pintype "unspecified"))
      (node (ref "USB13") (pin "B10") (pinfunction "SSRXn1_B10") (pintype "unspecified"))
      (node (ref "USB14") (pin "A10") (pinfunction "SSRXn2_A10") (pintype "unspecified"))
      (node (ref "USB14") (pin "B10") (pinfunction "SSRXn1_B10") (pintype "unspecified"))
      (node (ref "USB15") (pin "A10") (pinfunction "SSRXn2_A10") (pintype "unspecified"))
      (node (ref "USB15") (pin "B10") (pinfunction "SSRXn1_B10") (pintype "unspecified"))
      (node (ref "USB16") (pin "A10") (pinfunction "SSRXn2_A10") (pintype "unspecified"))
      (node (ref "USB16") (pin "B10") (pinfunction "SSRXn1_B10") (pintype "unspecified"))
      (node (ref "USB2") (pin "A10") (pinfunction "SSRXn2_A10") (pintype "unspecified"))
      (node (ref "USB2") (pin "B10") (pinfunction "SSRXn1_B10") (pintype "unspecified"))
      (node (ref "USB3") (pin "A10") (pinfunction "SSRXn2_A10") (pintype "unspecified"))
      (node (ref "USB3") (pin "B10") (pinfunction "SSRXn1_B10") (pintype "unspecified"))
      (node (ref "USB4") (pin "A10") (pinfunction "SSRXn2_A10") (pintype "unspecified"))
      (node (ref "USB4") (pin "B10") (pinfunction "SSRXn1_B10") (pintype "unspecified"))
      (node (ref "USB5") (pin "A10") (pinfunction "SSRXn2_A10") (pintype "unspecified"))
      (node (ref "USB5") (pin "B10") (pinfunction "SSRXn1_B10") (pintype "unspecified"))
      (node (ref "USB6") (pin "A10") (pinfunction "SSRXn2_A10") (pintype "unspecified"))
      (node (ref "USB6") (pin "B10") (pinfunction "SSRXn1_B10") (pintype "unspecified"))
      (node (ref "USB7") (pin "A10") (pinfunction "SSRXn2_A10") (pintype "unspecified"))
      (node (ref "USB7") (pin "B10") (pinfunction "SSRXn1_B10") (pintype "unspecified"))
      (node (ref "USB8") (pin "A10") (pinfunction "SSRXn2_A10") (pintype "unspecified"))
      (node (ref "USB8") (pin "B10") (pinfunction "SSRXn1_B10") (pintype "unspecified"))
      (node (ref "USB9") (pin "A10") (pinfunction "SSRXn2_A10") (pintype "unspecified"))
      (node (ref "USB9") (pin "B10") (pinfunction "SSRXn1_B10") (pintype "unspecified"))
    )
    (net (code "24") (name "/VIN") (class "Default")
      (node (ref "CN1") (pin "2") (pinfunction "+_2") (pintype "unspecified"))
      (node (ref "USB1") (pin "A4") (pinfunction "VBUS_A4") (pintype "unspecified"))
      (node (ref "USB1") (pin "A9") (pinfunction "VBUS_A9") (pintype "unspecified"))
      (node (ref "USB1") (pin "B4") (pinfunction "VBUS_B4") (pintype "unspecified"))
      (node (ref "USB1") (pin "B9") (pinfunction "VBUS_B9") (pintype "unspecified"))
      (node (ref "USB10") (pin "A4") (pinfunction "VBUS_A4") (pintype "unspecified"))
      (node (ref "USB10") (pin "A9") (pinfunction "VBUS_A9") (pintype "unspecified"))
      (node (ref "USB10") (pin "B4") (pinfunction "VBUS_B4") (pintype "unspecified"))
      (node (ref "USB10") (pin "B9") (pinfunction "VBUS_B9") (pintype "unspecified"))
      (node (ref "USB11") (pin "A4") (pinfunction "VBUS_A4") (pintype "unspecified"))
      (node (ref "USB11") (pin "A9") (pinfunction "VBUS_A9") (pintype "unspecified"))
      (node (ref "USB11") (pin "B4") (pinfunction "VBUS_B4") (pintype "unspecified"))
      (node (ref "USB11") (pin "B9") (pinfunction "VBUS_B9") (pintype "unspecified"))
      (node (ref "USB12") (pin "A4") (pinfunction "VBUS_A4") (pintype "unspecified"))
      (node (ref "USB12") (pin "A9") (pinfunction "VBUS_A9") (pintype "unspecified"))
      (node (ref "USB12") (pin "B4") (pinfunction "VBUS_B4") (pintype "unspecified"))
      (node (ref "USB12") (pin "B9") (pinfunction "VBUS_B9") (pintype "unspecified"))
      (node (ref "USB13") (pin "A4") (pinfunction "VBUS_A4") (pintype "unspecified"))
      (node (ref "USB13") (pin "A9") (pinfunction "VBUS_A9") (pintype "unspecified"))
      (node (ref "USB13") (pin "B4") (pinfunction "VBUS_B4") (pintype "unspecified"))
      (node (ref "USB13") (pin "B9") (pinfunction "VBUS_B9") (pintype "unspecified"))
      (node (ref "USB14") (pin "A4") (pinfunction "VBUS_A4") (pintype "unspecified"))
      (node (ref "USB14") (pin "A9") (pinfunction "VBUS_A9") (pintype "unspecified"))
      (node (ref "USB14") (pin "B4") (pinfunction "VBUS_B4") (pintype "unspecified"))
      (node (ref "USB14") (pin "B9") (pinfunction "VBUS_B9") (pintype "unspecified"))
      (node (ref "USB15") (pin "A4") (pinfunction "VBUS_A4") (pintype "unspecified"))
      (node (ref "USB15") (pin "A9") (pinfunction "VBUS_A9") (pintype "unspecified"))
      (node (ref "USB15") (pin "B4") (pinfunction "VBUS_B4") (pintype "unspecified"))
      (node (ref "USB15") (pin "B9") (pinfunction "VBUS_B9") (pintype "unspecified"))
      (node (ref "USB16") (pin "A4") (pinfunction "VBUS_A4") (pintype "unspecified"))
      (node (ref "USB16") (pin "A9") (pinfunction "VBUS_A9") (pintype "unspecified"))
      (node (ref "USB16") (pin "B4") (pinfunction "VBUS_B4") (pintype "unspecified"))
      (node (ref "USB16") (pin "B9") (pinfunction "VBUS_B9") (pintype "unspecified"))
      (node (ref "USB2") (pin "A4") (pinfunction "VBUS_A4") (pintype "unspecified"))
      (node (ref "USB2") (pin "A9") (pinfunction "VBUS_A9") (pintype "unspecified"))
      (node (ref "USB2") (pin "B4") (pinfunction "VBUS_B4") (pintype "unspecified"))
      (node (ref "USB2") (pin "B9") (pinfunction "VBUS_B9") (pintype "unspecified"))
      (node (ref "USB3") (pin "A4") (pinfunction "VBUS_A4") (pintype "unspecified"))
      (node (ref "USB3") (pin "A9") (pinfunction "VBUS_A9") (pintype "unspecified"))
      (node (ref "USB3") (pin "B4") (pinfunction "VBUS_B4") (pintype "unspecified"))
      (node (ref "USB3") (pin "B9") (pinfunction "VBUS_B9") (pintype "unspecified"))
      (node (ref "USB4") (pin "A4") (pinfunction "VBUS_A4") (pintype "unspecified"))
      (node (ref "USB4") (pin "A9") (pinfunction "VBUS_A9") (pintype "unspecified"))
      (node (ref "USB4") (pin "B4") (pinfunction "VBUS_B4") (pintype "unspecified"))
      (node (ref "USB4") (pin "B9") (pinfunction "VBUS_B9") (pintype "unspecified"))
      (node (ref "USB5") (pin "A4") (pinfunction "VBUS_A4") (pintype "unspecified"))
      (node (ref "USB5") (pin "A9") (pinfunction "VBUS_A9") (pintype "unspecified"))
      (node (ref "USB5") (pin "B4") (pinfunction "VBUS_B4") (pintype "unspecified"))
      (node (ref "USB5") (pin "B9") (pinfunction "VBUS_B9") (pintype "unspecified"))
      (node (ref "USB6") (pin "A4") (pinfunction "VBUS_A4") (pintype "unspecified"))
      (node (ref "USB6") (pin "A9") (pinfunction "VBUS_A9") (pintype "unspecified"))
      (node (ref "USB6") (pin "B4") (pinfunction "VBUS_B4") (pintype "unspecified"))
      (node (ref "USB6") (pin "B9") (pinfunction "VBUS_B9") (pintype "unspecified"))
      (node (ref "USB7") (pin "A4") (pinfunction "VBUS_A4") (pintype "unspecified"))
      (node (ref "USB7") (pin "A9") (pinfunction "VBUS_A9") (pintype "unspecified"))
      (node (ref "USB7") (pin "B4") (pinfunction "VBUS_B4") (pintype "unspecified"))
      (node (ref "USB7") (pin "B9") (pinfunction "VBUS_B9") (pintype "unspecified"))
      (node (ref "USB8") (pin "A4") (pinfunction "VBUS_A4") (pintype "unspecified"))
      (node (ref "USB8") (pin "A9") (pinfunction "VBUS_A9") (pintype "unspecified"))
      (node (ref "USB8") (pin "B4") (pinfunction "VBUS_B4") (pintype "unspecified"))
      (node (ref "USB8") (pin "B9") (pinfunction "VBUS_B9") (pintype "unspecified"))
      (node (ref "USB9") (pin "A4") (pinfunction "VBUS_A4") (pintype "unspecified"))
      (node (ref "USB9") (pin "A9") (pinfunction "VBUS_A9") (pintype "unspecified"))
      (node (ref "USB9") (pin "B4") (pinfunction "VBUS_B4") (pintype "unspecified"))
      (node (ref "USB9") (pin "B9") (pinfunction "VBUS_B9") (pintype "unspecified"))
    )
    (net (code "25") (name "GND") (class "Default")
      (node (ref "CN1") (pin "1") (pinfunction "-_1") (pintype "unspecified"))
      (node (ref "R1") (pin "2") (pinfunction "2_2") (pintype "input"))
      (node (ref "R10") (pin "2") (pinfunction "2_2") (pintype "input"))
      (node (ref "R11") (pin "2") (pinfunction "2_2") (pintype "input"))
      (node (ref "R12") (pin "2") (pinfunction "2_2") (pintype "input"))
      (node (ref "R13") (pin "2") (pinfunction "2_2") (pintype "input"))
      (node (ref "R14") (pin "2") (pinfunction "2_2") (pintype "input"))
      (node (ref "R15") (pin "2") (pinfunction "2_2") (pintype "input"))
      (node (ref "R16") (pin "2") (pinfunction "2_2") (pintype "input"))
      (node (ref "R2") (pin "2") (pinfunction "2_2") (pintype "input"))
      (node (ref "R3") (pin "2") (pinfunction "2_2") (pintype "input"))
      (node (ref "R4") (pin "2") (pinfunction "2_2") (pintype "input"))
      (node (ref "R5") (pin "2") (pinfunction "2_2") (pintype "input"))
      (node (ref "R6") (pin "2") (pinfunction "2_2") (pintype "input"))
      (node (ref "R7") (pin "2") (pinfunction "2_2") (pintype "input"))
      (node (ref "R8") (pin "2") (pinfunction "2_2") (pintype "input"))
      (node (ref "R9") (pin "2") (pinfunction "2_2") (pintype "input"))
      (node (ref "USB1") (pin "A1") (pinfunction "GND_A1") (pintype "unspecified"))
      (node (ref "USB1") (pin "A12") (pinfunction "GND_A12") (pintype "unspecified"))
      (node (ref "USB1") (pin "B1") (pinfunction "GND_B1") (pintype "unspecified"))
      (node (ref "USB1") (pin "B12") (pinfunction "GND_B12") (pintype "unspecified"))
      (node (ref "USB10") (pin "A1") (pinfunction "GND_A1") (pintype "unspecified"))
      (node (ref "USB10") (pin "A12") (pinfunction "GND_A12") (pintype "unspecified"))
      (node (ref "USB10") (pin "B1") (pinfunction "GND_B1") (pintype "unspecified"))
      (node (ref "USB10") (pin "B12") (pinfunction "GND_B12") (pintype "unspecified"))
      (node (ref "USB11") (pin "A1") (pinfunction "GND_A1") (pintype "unspecified"))
      (node (ref "USB11") (pin "A12") (pinfunction "GND_A12") (pintype "unspecified"))
      (node (ref "USB11") (pin "B1") (pinfunction "GND_B1") (pintype "unspecified"))
      (node (ref "USB11") (pin "B12") (pinfunction "GND_B12") (pintype "unspecified"))
      (node (ref "USB12") (pin "A1") (pinfunction "GND_A1") (pintype "unspecified"))
      (node (ref "USB12") (pin "A12") (pinfunction "GND_A12") (pintype "unspecified"))
      (node (ref "USB12") (pin "B1") (pinfunction "GND_B1") (pintype "unspecified"))
      (node (ref "USB12") (pin "B12") (pinfunction "GND_B12") (pintype "unspecified"))
      (node (ref "USB13") (pin "A1") (pinfunction "GND_A1") (pintype "unspecified"))
      (node (ref "USB13") (pin "A12") (pinfunction "GND_A12") (pintype "unspecified"))
      (node (ref "USB13") (pin "B1") (pinfunction "GND_B1") (pintype "unspecified"))
      (node (ref "USB13") (pin "B12") (pinfunction "GND_B12") (pintype "unspecified"))
      (node (ref "USB14") (pin "A1") (pinfunction "GND_A1") (pintype "unspecified"))
      (node (ref "USB14") (pin "A12") (pinfunction "GND_A12") (pintype "unspecified"))
      (node (ref "USB14") (pin "B1") (pinfunction "GND_B1") (pintype "unspecified"))
      (node (ref "USB14") (pin "B12") (pinfunction "GND_B12") (pintype "unspecified"))
      (node (ref "USB15") (pin "A1") (pinfunction "GND_A1") (pintype "unspecified"))
      (node (ref "USB15") (pin "A12") (pinfunction "GND_A12") (pintype "unspecified"))
      (node (ref "USB15") (pin "B1") (pinfunction "GND_B1") (pintype "unspecified"))
      (node (ref "USB15") (pin "B12") (pinfunction "GND_B12") (pintype "unspecified"))
      (node (ref "USB16") (pin "A1") (pinfunction "GND_A1") (pintype "unspecified"))
      (node (ref "USB16") (pin "A12") (pinfunction "GND_A12") (pintype "unspecified"))
      (node (ref "USB16") (pin "B1") (pinfunction "GND_B1") (pintype "unspecified"))
      (node (ref "USB16") (pin "B12") (pinfunction "GND_B12") (pintype "unspecified"))
      (node (ref "USB2") (pin "A1") (pinfunction "GND_A1") (pintype "unspecified"))
      (node (ref "USB2") (pin "A12") (pinfunction "GND_A12") (pintype "unspecified"))
      (node (ref "USB2") (pin "B1") (pinfunction "GND_B1") (pintype "unspecified"))
      (node (ref "USB2") (pin "B12") (pinfunction "GND_B12") (pintype "unspecified"))
      (node (ref "USB3") (pin "A1") (pinfunction "GND_A1") (pintype "unspecified"))
      (node (ref "USB3") (pin "A12") (pinfunction "GND_A12") (pintype "unspecified"))
      (node (ref "USB3") (pin "B1") (pinfunction "GND_B1") (pintype "unspecified"))
      (node (ref "USB3") (pin "B12") (pinfunction "GND_B12") (pintype "unspecified"))
      (node (ref "USB4") (pin "A1") (pinfunction "GND_A1") (pintype "unspecified"))
      (node (ref "USB4") (pin "A12") (pinfunction "GND_A12") (pintype "unspecified"))
      (node (ref "USB4") (pin "B1") (pinfunction "GND_B1") (pintype "unspecified"))
      (node (ref "USB4") (pin "B12") (pinfunction "GND_B12") (pintype "unspecified"))
      (node (ref "USB5") (pin "A1") (pinfunction "GND_A1") (pintype "unspecified"))
      (node (ref "USB5") (pin "A12") (pinfunction "GND_A12") (pintype "unspecified"))
      (node (ref "USB5") (pin "B1") (pinfunction "GND_B1") (pintype "unspecified"))
      (node (ref "USB5") (pin "B12") (pinfunction "GND_B12") (pintype "unspecified"))
      (node (ref "USB6") (pin "A1") (pinfunction "GND_A1") (pintype "unspecified"))
      (node (ref "USB6") (pin "A12") (pinfunction "GND_A12") (pintype "unspecified"))
      (node (ref "USB6") (pin "B1") (pinfunction "GND_B1") (pintype "unspecified"))
      (node (ref "USB6") (pin "B12") (pinfunction "GND_B12") (pintype "unspecified"))
      (node (ref "USB7") (pin "A1") (pinfunction "GND_A1") (pintype "unspecified"))
      (node (ref "USB7") (pin "A12") (pinfunction "GND_A12") (pintype "unspecified"))
      (node (ref "USB7") (pin "B1") (pinfunction "GND_B1") (pintype "unspecified"))
      (node (ref "USB7") (pin "B12") (pinfunction "GND_B12") (pintype "unspecified"))
      (node (ref "USB8") (pin "A1") (pinfunction "GND_A1") (pintype "unspecified"))
      (node (ref "USB8") (pin "A12") (pinfunction "GND_A12") (pintype "unspecified"))
      (node (ref "USB8") (pin "B1") (pinfunction "GND_B1") (pintype "unspecified"))
      (node (ref "USB8") (pin "B12") (pinfunction "GND_B12") (pintype "unspecified"))
      (node (ref "USB9") (pin "A1") (pinfunction "GND_A1") (pintype "unspecified"))
      (node (ref "USB9") (pin "A12") (pinfunction "GND_A12") (pintype "unspecified"))
      (node (ref "USB9") (pin "B1") (pinfunction "GND_B1") (pintype "unspecified"))
      (node (ref "USB9") (pin "B12") (pinfunction "GND_B12") (pintype "unspecified"))
    )
    (net (code "26") (name "Net-(LED1-C)") (class "Default")
      (node (ref "LED1") (pin "1") (pinfunction "C_1") (pintype "input"))
      (node (ref "R1") (pin "1") (pinfunction "1_1") (pintype "input"))
    )
    (net (code "27") (name "Net-(LED2-C)") (class "Default")
      (node (ref "LED2") (pin "1") (pinfunction "C_1") (pintype "input"))
      (node (ref "R2") (pin "1") (pinfunction "1_1") (pintype "input"))
    )
    (net (code "28") (name "Net-(LED3-C)") (class "Default")
      (node (ref "LED3") (pin "1") (pinfunction "C_1") (pintype "input"))
      (node (ref "R3") (pin "1") (pinfunction "1_1") (pintype "input"))
    )
    (net (code "29") (name "Net-(LED4-C)") (class "Default")
      (node (ref "LED4") (pin "1") (pinfunction "C_1") (pintype "input"))
      (node (ref "R4") (pin "1") (pinfunction "1_1") (pintype "input"))
    )
    (net (code "30") (name "Net-(LED5-C)") (class "Default")
      (node (ref "LED5") (pin "1") (pinfunction "C_1") (pintype "input"))
      (node (ref "R5") (pin "1") (pinfunction "1_1") (pintype "input"))
    )
    (net (code "31") (name "Net-(LED6-C)") (class "Default")
      (node (ref "LED6") (pin "1") (pinfunction "C_1") (pintype "input"))
      (node (ref "R6") (pin "1") (pinfunction "1_1") (pintype "input"))
    )
    (net (code "32") (name "Net-(LED7-C)") (class "Default")
      (node (ref "LED7") (pin "1") (pinfunction "C_1") (pintype "input"))
      (node (ref "R7") (pin "1") (pinfunction "1_1") (pintype "input"))
    )
    (net (code "33") (name "Net-(LED8-C)") (class "Default")
      (node (ref "LED8") (pin "1") (pinfunction "C_1") (pintype "input"))
      (node (ref "R8") (pin "1") (pinfunction "1_1") (pintype "input"))
    )
    (net (code "34") (name "Net-(LED9-C)") (class "Default")
      (node (ref "LED9") (pin "1") (pinfunction "C_1") (pintype "input"))
      (node (ref "R9") (pin "1") (pinfunction "1_1") (pintype "input"))
    )
    (net (code "35") (name "Net-(LED10-C)") (class "Default")
      (node (ref "LED10") (pin "1") (pinfunction "C_1") (pintype "input"))
      (node (ref "R10") (pin "1") (pinfunction "1_1") (pintype "input"))
    )
    (net (code "36") (name "Net-(LED11-C)") (class "Default")
      (node (ref "LED11") (pin "1") (pinfunction "C_1") (pintype "input"))
      (node (ref "R11") (pin "1") (pinfunction "1_1") (pintype "input"))
    )
    (net (code "37") (name "Net-(LED12-C)") (class "Default")
      (node (ref "LED12") (pin "1") (pinfunction "C_1") (pintype "input"))
      (node (ref "R12") (pin "1") (pinfunction "1_1") (pintype "input"))
    )
    (net (code "38") (name "Net-(LED13-C)") (class "Default")
      (node (ref "LED13") (pin "1") (pinfunction "C_1") (pintype "input"))
      (node (ref "R13") (pin "1") (pinfunction "1_1") (pintype "input"))
    )
    (net (code "39") (name "Net-(LED14-C)") (class "Default")
      (node (ref "LED14") (pin "1") (pinfunction "C_1") (pintype "input"))
      (node (ref "R14") (pin "1") (pinfunction "1_1") (pintype "input"))
    )
    (net (code "40") (name "Net-(LED15-C)") (class "Default")
      (node (ref "LED15") (pin "1") (pinfunction "C_1") (pintype "input"))
      (node (ref "R15") (pin "1") (pinfunction "1_1") (pintype "input"))
    )
    (net (code "41") (name "Net-(LED16-C)") (class "Default")
      (node (ref "LED16") (pin "1") (pinfunction "C_1") (pintype "input"))
      (node (ref "R16") (pin "1") (pinfunction "1_1") (pintype "input"))
    )
    (net (code "42") (name "unconnected-(CN1-Pad3)") (class "Default")
      (node (ref "CN1") (pin "3") (pinfunction "3_3") (pintype "unspecified+no_connect"))
    )
    (net (code "43") (name "unconnected-(CN1-Pad4)") (class "Default")
      (node (ref "CN1") (pin "4") (pinfunction "4_4") (pintype "unspecified+no_connect"))
    )
    (net (code "44") (name "unconnected-(USB1-EH-Pad25)") (class "Default")
      (node (ref "USB1") (pin "25") (pinfunction "EH_25") (pintype "unspecified+no_connect"))
    )
    (net (code "45") (name "unconnected-(USB2-EH-Pad25)") (class "Default")
      (node (ref "USB2") (pin "25") (pinfunction "EH_25") (pintype "unspecified+no_connect"))
    )
    (net (code "46") (name "unconnected-(USB3-EH-Pad25)") (class "Default")
      (node (ref "USB3") (pin "25") (pinfunction "EH_25") (pintype "unspecified+no_connect"))
    )
    (net (code "47") (name "unconnected-(USB4-EH-Pad25)") (class "Default")
      (node (ref "USB4") (pin "25") (pinfunction "EH_25") (pintype "unspecified+no_connect"))
    )
    (net (code "48") (name "unconnected-(USB5-EH-Pad25)") (class "Default")
      (node (ref "USB5") (pin "25") (pinfunction "EH_25") (pintype "unspecified+no_connect"))
    )
    (net (code "49") (name "unconnected-(USB6-EH-Pad25)") (class "Default")
      (node (ref "USB6") (pin "25") (pinfunction "EH_25") (pintype "unspecified+no_connect"))
    )
    (net (code "50") (name "unconnected-(USB7-EH-Pad25)") (class "Default")
      (node (ref "USB7") (pin "25") (pinfunction "EH_25") (pintype "unspecified+no_connect"))
    )
    (net (code "51") (name "unconnected-(USB8-EH-Pad25)") (class "Default")
      (node (ref "USB8") (pin "25") (pinfunction "EH_25") (pintype "unspecified+no_connect"))
    )
    (net (code "52") (name "unconnected-(USB9-EH-Pad25)") (class "Default")
      (node (ref "USB9") (pin "25") (pinfunction "EH_25") (pintype "unspecified+no_connect"))
    )
    (net (code "53") (name "unconnected-(USB10-EH-Pad25)") (class "Default")
      (node (ref "USB10") (pin "25") (pinfunction "EH_25") (pintype "unspecified+no_connect"))
    )
    (net (code "54") (name "unconnected-(USB11-EH-Pad25)") (class "Default")
      (node (ref "USB11") (pin "25") (pinfunction "EH_25") (pintype "unspecified+no_connect"))
    )
    (net (code "55") (name "unconnected-(USB12-EH-Pad25)") (class "Default")
      (node (ref "USB12") (pin "25") (pinfunction "EH_25") (pintype "unspecified+no_connect"))
    )
    (net (code "56") (name "unconnected-(USB13-EH-Pad25)") (class "Default")
      (node (ref "USB13") (pin "25") (pinfunction "EH_25") (pintype "unspecified+no_connect"))
    )
    (net (code "57") (name "unconnected-(USB14-EH-Pad25)") (class "Default")
      (node (ref "USB14") (pin "25") (pinfunction "EH_25") (pintype "unspecified+no_connect"))
    )
    (net (code "58") (name "unconnected-(USB15-EH-Pad25)") (class "Default")
      (node (ref "USB15") (pin "25") (pinfunction "EH_25") (pintype "unspecified+no_connect"))
    )
    (net (code "59") (name "unconnected-(USB16-EH-Pad25)") (class "Default")
      (node (ref "USB16") (pin "25") (pinfunction "EH_25") (pintype "unspecified+no_connect"))
    )
  )
)
